# attiny85-mini-mk-2_0.net
KiCad netlist of a schematic drawn in EAGLE
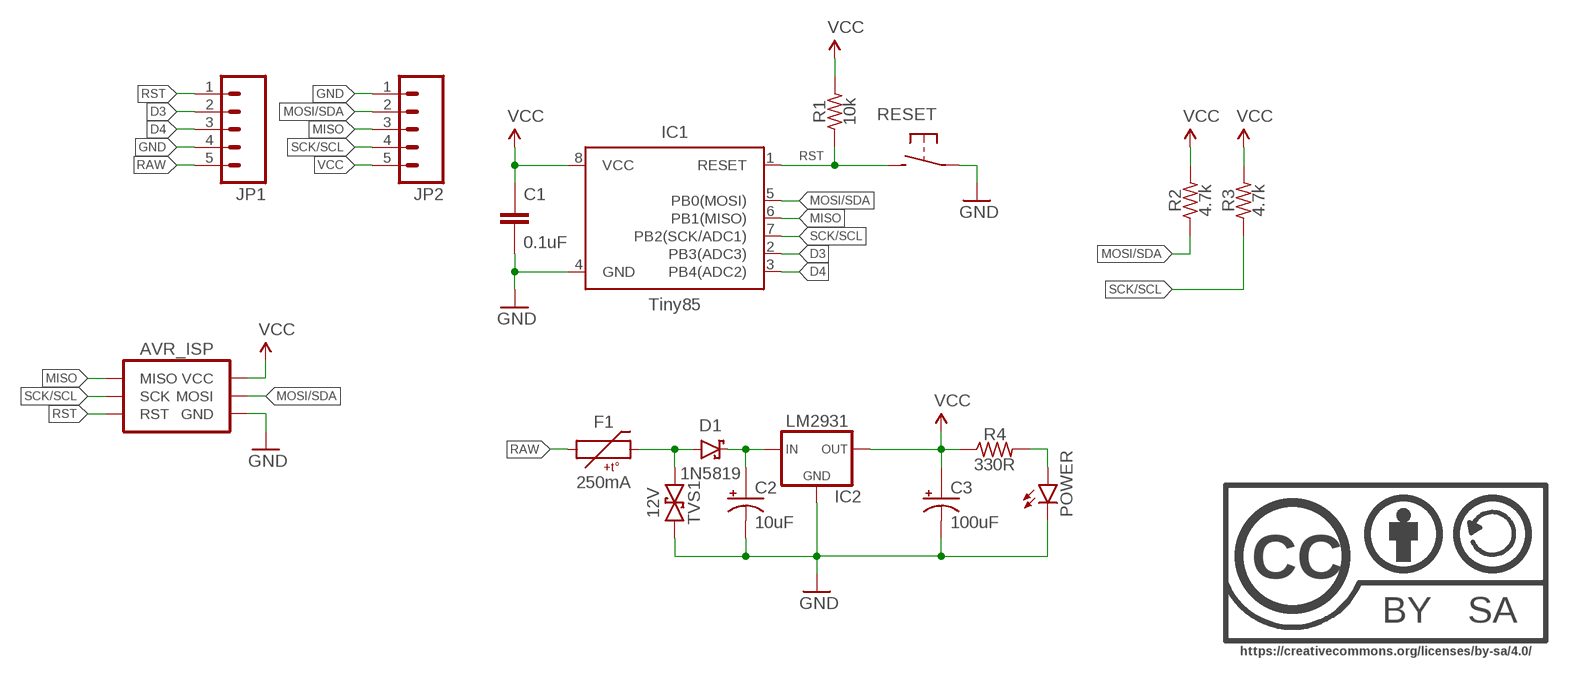
[diagram p0: schematic, sheet 1]

(export (version "E")
  (design (tool "Eeschema 10.0.6"))
  (components
    (comp (ref "AVR_ISP")
      (value "AVR_SPI_PRG_6PTH")
      (footprint "eagle-import:2X3")
      (libsource (lib "eagle-import") (part "AVR_SPI_PRG_6PTH"))
    )
    (comp (ref "C1")
      (value "0.1uF")
      (footprint "eagle-import:C025-024X044")
      (libsource (lib "eagle-import") (part "CAPACITOR-CERAMIC025-024X044"))
    )
    (comp (ref "C2")
      (value "10uF")
      (footprint "eagle-import:E2-5")
      (libsource (lib "eagle-import") (part "CAPACITOR-POLARIZEDE2-5"))
    )
    (comp (ref "C3")
      (value "100uF")
      (footprint "eagle-import:E2,5-5")
      (libsource (lib "eagle-import") (part "CAPACITOR-POLARIZEDE2.5-5"))
    )
    (comp (ref "D1")
      (value "1N5819")
      (footprint "eagle-import:DIODE-10.16MM")
      (libsource (lib "eagle-import") (part "DIODE-SCHOTTKYPTH-10.16MM"))
    )
    (comp (ref "F1")
      (value "250mA")
      (footprint "eagle-import:PTC-PTH-5.08MM")
      (libsource (lib "eagle-import") (part "PTCPTH-5.08MM"))
    )
    (comp (ref "IC1")
      (value "Tiny85")
      (footprint "eagle-import:DIP08")
      (libsource (lib "eagle-import") (part "ATTINY45TINY85-20-DIP"))
    )
    (comp (ref "IC2")
      (value "LM2931")
      (footprint "eagle-import:TO-92-AMMO")
      (libsource (lib "eagle-import") (part "V_REG_78XXTO-92-INLINE"))
    )
    (comp (ref "JP1")
      (value "M05PTH")
      (footprint "eagle-import:1X05")
      (libsource (lib "eagle-import") (part "M05PTH"))
    )
    (comp (ref "JP2")
      (value "M05PTH")
      (footprint "eagle-import:1X05")
      (libsource (lib "eagle-import") (part "M05PTH"))
    )
    (comp (ref "POWER")
      (value "LED3MM-LESS")
      (footprint "eagle-import:LED3MM-LESSSILK")
      (libsource (lib "eagle-import") (part "LED3MM-LESS"))
    )
    (comp (ref "R1")
      (value "10k")
      (footprint "eagle-import:RESISTOR-AXIAL-PTH-5.08MM")
      (libsource (lib "eagle-import") (part "RESISTORPTH-AXIAL-5.08MM"))
    )
    (comp (ref "R2")
      (value "4.7k")
      (footprint "eagle-import:RESISTOR-AXIAL-PTH-5.08MM")
      (libsource (lib "eagle-import") (part "RESISTORPTH-AXIAL-5.08MM"))
    )
    (comp (ref "R3")
      (value "4.7k")
      (footprint "eagle-import:RESISTOR-AXIAL-PTH-5.08MM")
      (libsource (lib "eagle-import") (part "RESISTORPTH-AXIAL-5.08MM"))
    )
    (comp (ref "R4")
      (value "330R")
      (footprint "eagle-import:RESISTOR-AXIAL-PTH-5.08MM")
      (libsource (lib "eagle-import") (part "RESISTORPTH-AXIAL-5.08MM"))
    )
    (comp (ref "RESET")
      (value "DTS-6MM")
      (footprint "eagle-import:DTS-3-SMALL-PADS")
      (libsource (lib "eagle-import") (part "SPST-NO-TACT3MM-PTH-SMALL-PADS"))
    )
    (comp (ref "TVS1")
      (value "12V")
      (footprint "eagle-import:DO-41-TVS")
      (libsource (lib "eagle-import") (part "TVSDO-41-TVS-BIDIRECTIONAL"))
    )
    (comp (ref "U$1")
      (value "CC-BY-SA-4.0NO-URL")
      (footprint "eagle-import:CC-BY-SA-4.0-NO-URL")
      (libsource (lib "eagle-import") (part "CC-BY-SA-4.0NO-URL"))
    )
  )
  (nets
    (net (code "1") (name "D3") (class "Default")
      (node (ref "IC1") (pin "2") (pinfunction "PB3(ADC3)_2") (pintype "bidirectional"))
      (node (ref "JP1") (pin "2") (pinfunction "2_2") (pintype "passive"))
    )
    (net (code "2") (name "D4") (class "Default")
      (node (ref "IC1") (pin "3") (pinfunction "PB4(ADC2)_3") (pintype "bidirectional"))
      (node (ref "JP1") (pin "3") (pinfunction "3_3") (pintype "passive"))
    )
    (net (code "3") (name "GND") (class "Default")
      (node (ref "AVR_ISP") (pin "6") (pinfunction "GND_6") (pintype "passive"))
      (node (ref "C1") (pin "2") (pinfunction "2_2") (pintype "passive"))
      (node (ref "C2") (pin "-") (pinfunction "-_-") (pintype "passive"))
      (node (ref "C3") (pin "-") (pinfunction "-_-") (pintype "passive"))
      (node (ref "IC1") (pin "4") (pinfunction "GND_4") (pintype "bidirectional"))
      (node (ref "IC2") (pin "2") (pinfunction "GND_2") (pintype "bidirectional"))
      (node (ref "JP1") (pin "4") (pinfunction "4_4") (pintype "passive"))
      (node (ref "JP2") (pin "1") (pinfunction "1_1") (pintype "passive"))
      (node (ref "POWER") (pin "K") (pinfunction "C_K") (pintype "passive"))
      (node (ref "RESET") (pin "1") (pinfunction "1_1") (pintype "passive"))
      (node (ref "TVS1") (pin "P$2") (pinfunction "2_P$2") (pintype "passive"))
    )
    (net (code "4") (name "MISO") (class "Default")
      (node (ref "AVR_ISP") (pin "1") (pinfunction "MISO_1") (pintype "passive"))
      (node (ref "IC1") (pin "6") (pinfunction "PB1(MISO)_6") (pintype "bidirectional"))
      (node (ref "JP2") (pin "3") (pinfunction "3_3") (pintype "passive"))
    )
    (net (code "5") (name "MOSI{slash}SDA") (class "Default")
      (node (ref "AVR_ISP") (pin "4") (pinfunction "MOSI_4") (pintype "passive"))
      (node (ref "IC1") (pin "5") (pinfunction "PB0(MOSI)_5") (pintype "bidirectional"))
      (node (ref "JP2") (pin "2") (pinfunction "2_2") (pintype "passive"))
      (node (ref "R2") (pin "P$1") (pinfunction "1_P$1") (pintype "passive"))
    )
    (net (code "6") (name "Net-(F1-2)") (class "Default")
      (node (ref "D1") (pin "A") (pinfunction "A_A") (pintype "passive"))
      (node (ref "F1") (pin "P$2") (pinfunction "2_P$2") (pintype "passive"))
      (node (ref "TVS1") (pin "P$1") (pinfunction "1_P$1") (pintype "passive"))
    )
    (net (code "7") (name "Net-(IC2-IN)") (class "Default")
      (node (ref "C2") (pin "+") (pinfunction "+_+") (pintype "passive"))
      (node (ref "D1") (pin "C") (pinfunction "C_C") (pintype "passive"))
      (node (ref "IC2") (pin "1") (pinfunction "IN_1") (pintype "bidirectional"))
    )
    (net (code "8") (name "Net-(R4-2)") (class "Default")
      (node (ref "POWER") (pin "A") (pinfunction "A_A") (pintype "passive"))
      (node (ref "R4") (pin "P$2") (pinfunction "2_P$2") (pintype "passive"))
    )
    (net (code "9") (name "RAW") (class "Default")
      (node (ref "F1") (pin "P$1") (pinfunction "1_P$1") (pintype "passive"))
      (node (ref "JP1") (pin "5") (pinfunction "5_5") (pintype "passive"))
    )
    (net (code "10") (name "RST") (class "Default")
      (node (ref "AVR_ISP") (pin "5") (pinfunction "RST_5") (pintype "passive"))
      (node (ref "IC1") (pin "1") (pinfunction "RESET_1") (pintype "bidirectional"))
      (node (ref "JP1") (pin "1") (pinfunction "1_1") (pintype "passive"))
      (node (ref "R1") (pin "P$1") (pinfunction "1_P$1") (pintype "passive"))
      (node (ref "RESET") (pin "2") (pinfunction "2_2") (pintype "passive"))
    )
    (net (code "11") (name "SCK{slash}SCL") (class "Default")
      (node (ref "AVR_ISP") (pin "3") (pinfunction "SCK_3") (pintype "passive"))
      (node (ref "IC1") (pin "7") (pinfunction "PB2(SCK/ADC1)_7") (pintype "bidirectional"))
      (node (ref "JP2") (pin "4") (pinfunction "4_4") (pintype "passive"))
      (node (ref "R3") (pin "P$1") (pinfunction "1_P$1") (pintype "passive"))
    )
    (net (code "12") (name "VCC") (class "Default")
      (node (ref "AVR_ISP") (pin "2") (pinfunction "VCC_2") (pintype "passive"))
      (node (ref "C1") (pin "1") (pinfunction "1_1") (pintype "passive"))
      (node (ref "C3") (pin "+") (pinfunction "+_+") (pintype "passive"))
      (node (ref "IC1") (pin "8") (pinfunction "VCC_8") (pintype "bidirectional"))
      (node (ref "IC2") (pin "3") (pinfunction "OUT_3") (pintype "bidirectional"))
      (node (ref "JP2") (pin "5") (pinfunction "5_5") (pintype "passive"))
      (node (ref "R1") (pin "P$2") (pinfunction "2_P$2") (pintype "passive"))
      (node (ref "R2") (pin "P$2") (pinfunction "2_P$2") (pintype "passive"))
      (node (ref "R3") (pin "P$2") (pinfunction "2_P$2") (pintype "passive"))
      (node (ref "R4") (pin "P$1") (pinfunction "1_P$1") (pintype "passive"))
    )
  )
)
